# 18650_tester_5.net
KiCad netlist of a schematic drawn in EAGLE
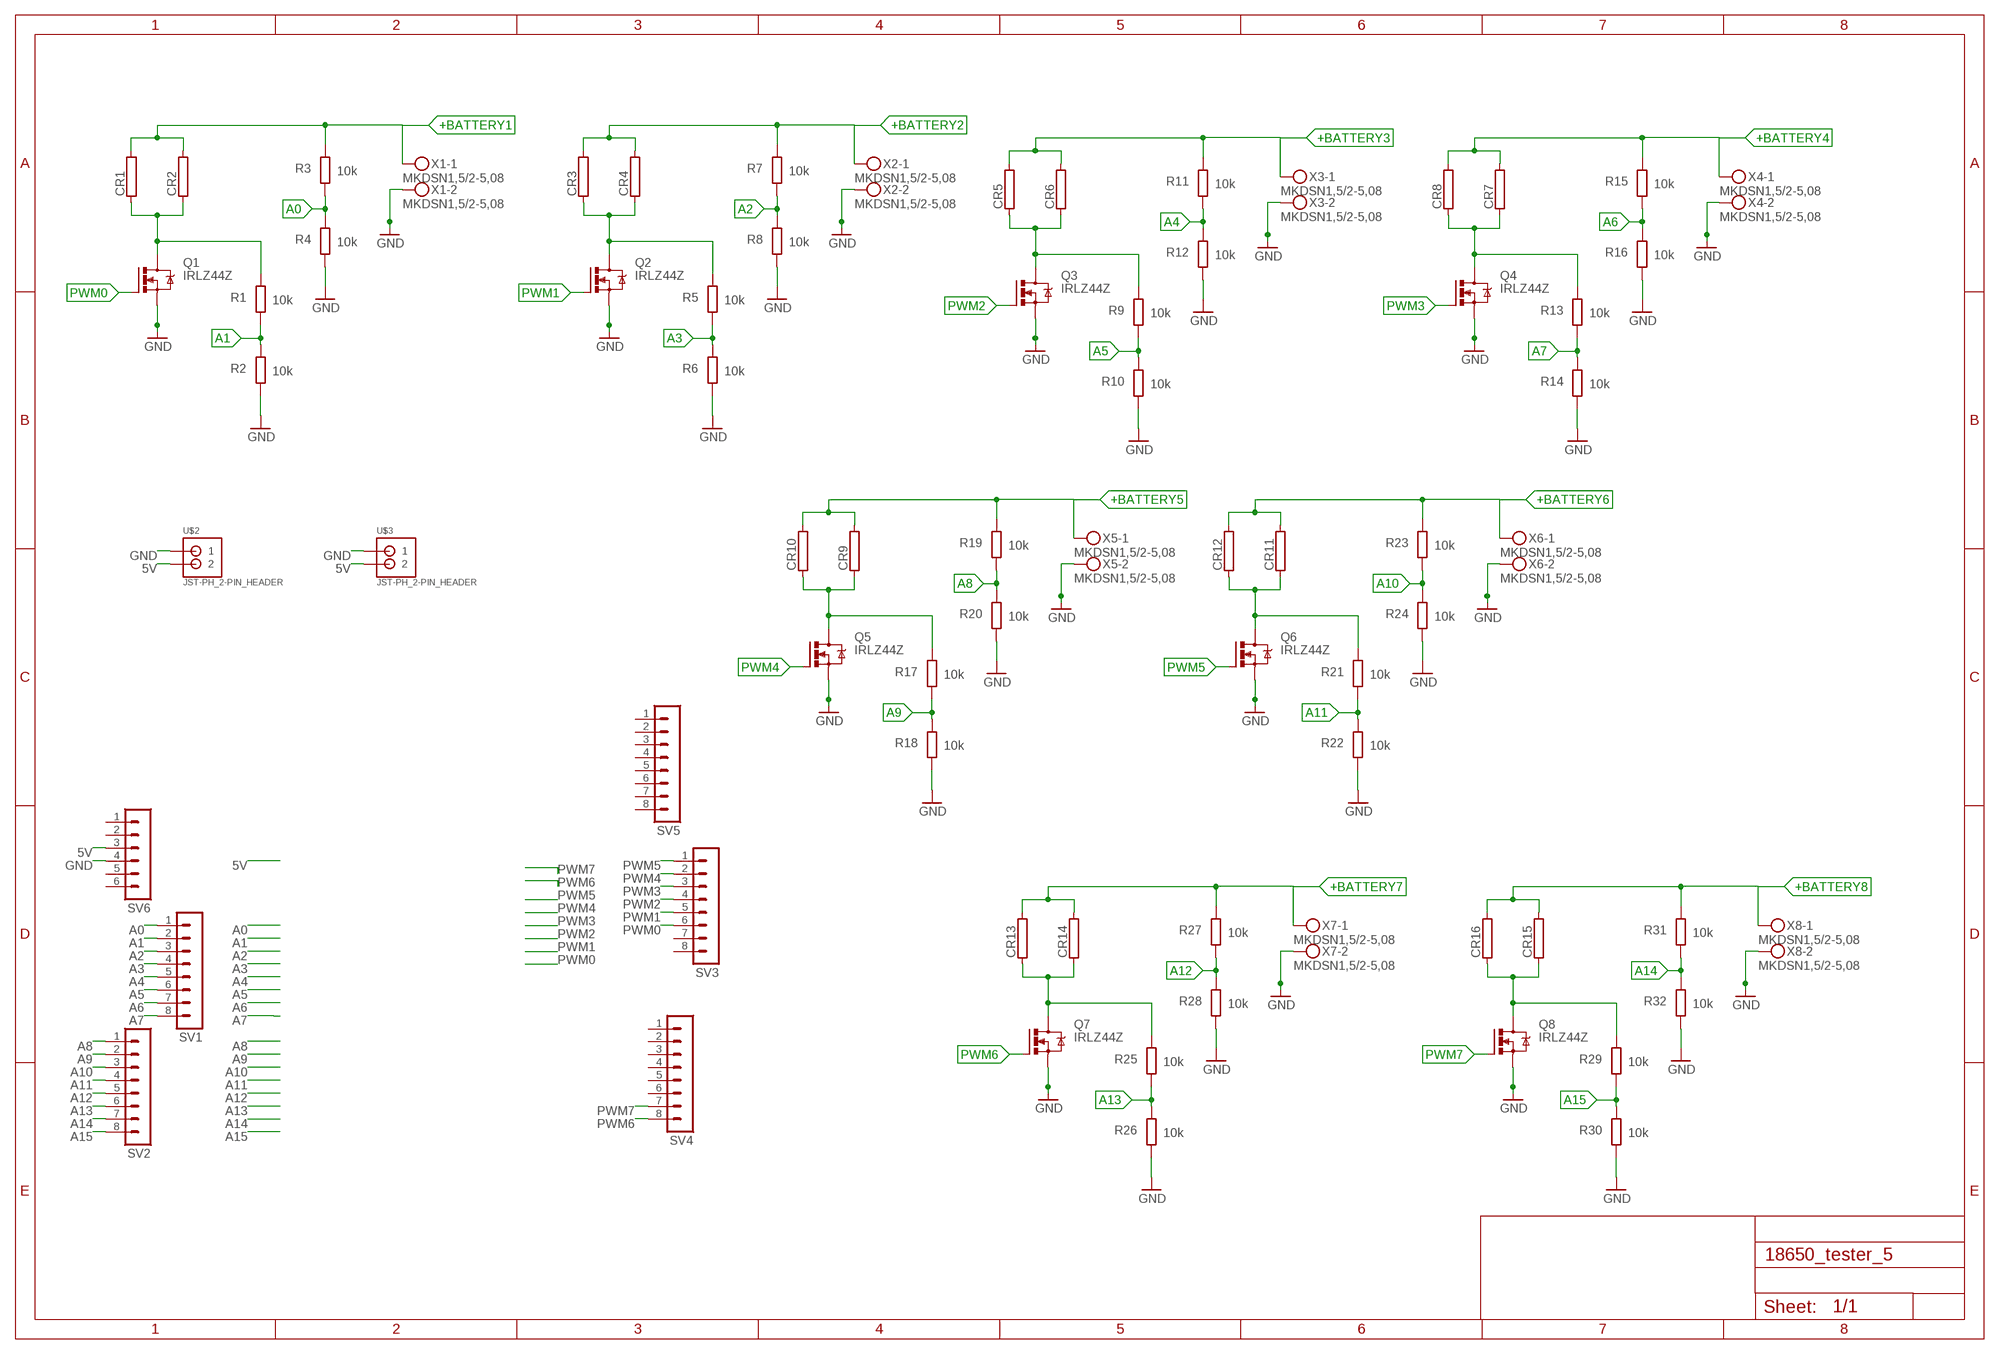
[diagram p0: schematic, sheet 1]

(export (version "E")
  (design (tool "Eeschema 10.0.6"))
  (components
    (comp (ref "CR1")
      (value "RRWM6X22")
      (footprint "eagle-import:RWM6X22")
      (libsource (lib "eagle-import") (part "RRWM6X22"))
    )
    (comp (ref "CR2")
      (value "RRWM6X22")
      (footprint "eagle-import:RWM6X22")
      (libsource (lib "eagle-import") (part "RRWM6X22"))
    )
    (comp (ref "CR3")
      (value "RRWM6X22")
      (footprint "eagle-import:RWM6X22")
      (libsource (lib "eagle-import") (part "RRWM6X22"))
    )
    (comp (ref "CR4")
      (value "RRWM6X22")
      (footprint "eagle-import:RWM6X22")
      (libsource (lib "eagle-import") (part "RRWM6X22"))
    )
    (comp (ref "CR5")
      (value "RRWM6X22")
      (footprint "eagle-import:RWM6X22")
      (libsource (lib "eagle-import") (part "RRWM6X22"))
    )
    (comp (ref "CR6")
      (value "RRWM6X22")
      (footprint "eagle-import:RWM6X22")
      (libsource (lib "eagle-import") (part "RRWM6X22"))
    )
    (comp (ref "CR7")
      (value "RRWM6X22")
      (footprint "eagle-import:RWM6X22")
      (libsource (lib "eagle-import") (part "RRWM6X22"))
    )
    (comp (ref "CR8")
      (value "RRWM6X22")
      (footprint "eagle-import:RWM6X22")
      (libsource (lib "eagle-import") (part "RRWM6X22"))
    )
    (comp (ref "CR9")
      (value "RRWM6X22")
      (footprint "eagle-import:RWM6X22")
      (libsource (lib "eagle-import") (part "RRWM6X22"))
    )
    (comp (ref "CR10")
      (value "RRWM6X22")
      (footprint "eagle-import:RWM6X22")
      (libsource (lib "eagle-import") (part "RRWM6X22"))
    )
    (comp (ref "CR11")
      (value "RRWM6X22")
      (footprint "eagle-import:RWM6X22")
      (libsource (lib "eagle-import") (part "RRWM6X22"))
    )
    (comp (ref "CR12")
      (value "RRWM6X22")
      (footprint "eagle-import:RWM6X22")
      (libsource (lib "eagle-import") (part "RRWM6X22"))
    )
    (comp (ref "CR13")
      (value "RRWM6X22")
      (footprint "eagle-import:RWM6X22")
      (libsource (lib "eagle-import") (part "RRWM6X22"))
    )
    (comp (ref "CR14")
      (value "RRWM6X22")
      (footprint "eagle-import:RWM6X22")
      (libsource (lib "eagle-import") (part "RRWM6X22"))
    )
    (comp (ref "CR15")
      (value "RRWM6X22")
      (footprint "eagle-import:RWM6X22")
      (libsource (lib "eagle-import") (part "RRWM6X22"))
    )
    (comp (ref "CR16")
      (value "RRWM6X22")
      (footprint "eagle-import:RWM6X22")
      (libsource (lib "eagle-import") (part "RRWM6X22"))
    )
    (comp (ref "Q1")
      (value "IRLZ44Z")
      (footprint "eagle-import:TO220BH")
      (libsource (lib "eagle-import") (part "IRLZ44Z"))
    )
    (comp (ref "Q2")
      (value "IRLZ44Z")
      (footprint "eagle-import:TO220BH")
      (libsource (lib "eagle-import") (part "IRLZ44Z"))
    )
    (comp (ref "Q3")
      (value "IRLZ44Z")
      (footprint "eagle-import:TO220BH")
      (libsource (lib "eagle-import") (part "IRLZ44Z"))
    )
    (comp (ref "Q4")
      (value "IRLZ44Z")
      (footprint "eagle-import:TO220BH")
      (libsource (lib "eagle-import") (part "IRLZ44Z"))
    )
    (comp (ref "Q5")
      (value "IRLZ44Z")
      (footprint "eagle-import:TO220BH")
      (libsource (lib "eagle-import") (part "IRLZ44Z"))
    )
    (comp (ref "Q6")
      (value "IRLZ44Z")
      (footprint "eagle-import:TO220BH")
      (libsource (lib "eagle-import") (part "IRLZ44Z"))
    )
    (comp (ref "Q7")
      (value "IRLZ44Z")
      (footprint "eagle-import:TO220BH")
      (libsource (lib "eagle-import") (part "IRLZ44Z"))
    )
    (comp (ref "Q8")
      (value "IRLZ44Z")
      (footprint "eagle-import:TO220BH")
      (libsource (lib "eagle-import") (part "IRLZ44Z"))
    )
    (comp (ref "R1")
      (value "10k")
      (footprint "eagle-import:M1206")
      (libsource (lib "eagle-import") (part "R-EU_M1206"))
    )
    (comp (ref "R2")
      (value "10k")
      (footprint "eagle-import:M1206")
      (libsource (lib "eagle-import") (part "R-EU_M1206"))
    )
    (comp (ref "R3")
      (value "10k")
      (footprint "eagle-import:M1206")
      (libsource (lib "eagle-import") (part "R-EU_M1206"))
    )
    (comp (ref "R4")
      (value "10k")
      (footprint "eagle-import:M1206")
      (libsource (lib "eagle-import") (part "R-EU_M1206"))
    )
    (comp (ref "R5")
      (value "10k")
      (footprint "eagle-import:M1206")
      (libsource (lib "eagle-import") (part "R-EU_M1206"))
    )
    (comp (ref "R6")
      (value "10k")
      (footprint "eagle-import:M1206")
      (libsource (lib "eagle-import") (part "R-EU_M1206"))
    )
    (comp (ref "R7")
      (value "10k")
      (footprint "eagle-import:M1206")
      (libsource (lib "eagle-import") (part "R-EU_M1206"))
    )
    (comp (ref "R8")
      (value "10k")
      (footprint "eagle-import:M1206")
      (libsource (lib "eagle-import") (part "R-EU_M1206"))
    )
    (comp (ref "R9")
      (value "10k")
      (footprint "eagle-import:M1206")
      (libsource (lib "eagle-import") (part "R-EU_M1206"))
    )
    (comp (ref "R10")
      (value "10k")
      (footprint "eagle-import:M1206")
      (libsource (lib "eagle-import") (part "R-EU_M1206"))
    )
    (comp (ref "R11")
      (value "10k")
      (footprint "eagle-import:M1206")
      (libsource (lib "eagle-import") (part "R-EU_M1206"))
    )
    (comp (ref "R12")
      (value "10k")
      (footprint "eagle-import:M1206")
      (libsource (lib "eagle-import") (part "R-EU_M1206"))
    )
    (comp (ref "R13")
      (value "10k")
      (footprint "eagle-import:M1206")
      (libsource (lib "eagle-import") (part "R-EU_M1206"))
    )
    (comp (ref "R14")
      (value "10k")
      (footprint "eagle-import:M1206")
      (libsource (lib "eagle-import") (part "R-EU_M1206"))
    )
    (comp (ref "R15")
      (value "10k")
      (footprint "eagle-import:M1206")
      (libsource (lib "eagle-import") (part "R-EU_M1206"))
    )
    (comp (ref "R16")
      (value "10k")
      (footprint "eagle-import:M1206")
      (libsource (lib "eagle-import") (part "R-EU_M1206"))
    )
    (comp (ref "R17")
      (value "10k")
      (footprint "eagle-import:M1206")
      (libsource (lib "eagle-import") (part "R-EU_M1206"))
    )
    (comp (ref "R18")
      (value "10k")
      (footprint "eagle-import:M1206")
      (libsource (lib "eagle-import") (part "R-EU_M1206"))
    )
    (comp (ref "R19")
      (value "10k")
      (footprint "eagle-import:M1206")
      (libsource (lib "eagle-import") (part "R-EU_M1206"))
    )
    (comp (ref "R20")
      (value "10k")
      (footprint "eagle-import:M1206")
      (libsource (lib "eagle-import") (part "R-EU_M1206"))
    )
    (comp (ref "R21")
      (value "10k")
      (footprint "eagle-import:M1206")
      (libsource (lib "eagle-import") (part "R-EU_M1206"))
    )
    (comp (ref "R22")
      (value "10k")
      (footprint "eagle-import:M1206")
      (libsource (lib "eagle-import") (part "R-EU_M1206"))
    )
    (comp (ref "R23")
      (value "10k")
      (footprint "eagle-import:M1206")
      (libsource (lib "eagle-import") (part "R-EU_M1206"))
    )
    (comp (ref "R24")
      (value "10k")
      (footprint "eagle-import:M1206")
      (libsource (lib "eagle-import") (part "R-EU_M1206"))
    )
    (comp (ref "R25")
      (value "10k")
      (footprint "eagle-import:M1206")
      (libsource (lib "eagle-import") (part "R-EU_M1206"))
    )
    (comp (ref "R26")
      (value "10k")
      (footprint "eagle-import:M1206")
      (libsource (lib "eagle-import") (part "R-EU_M1206"))
    )
    (comp (ref "R27")
      (value "10k")
      (footprint "eagle-import:M1206")
      (libsource (lib "eagle-import") (part "R-EU_M1206"))
    )
    (comp (ref "R28")
      (value "10k")
      (footprint "eagle-import:M1206")
      (libsource (lib "eagle-import") (part "R-EU_M1206"))
    )
    (comp (ref "R29")
      (value "10k")
      (footprint "eagle-import:M1206")
      (libsource (lib "eagle-import") (part "R-EU_M1206"))
    )
    (comp (ref "R30")
      (value "10k")
      (footprint "eagle-import:M1206")
      (libsource (lib "eagle-import") (part "R-EU_M1206"))
    )
    (comp (ref "R31")
      (value "10k")
      (footprint "eagle-import:M1206")
      (libsource (lib "eagle-import") (part "R-EU_M1206"))
    )
    (comp (ref "R32")
      (value "10k")
      (footprint "eagle-import:M1206")
      (libsource (lib "eagle-import") (part "R-EU_M1206"))
    )
    (comp (ref "SV1")
      (value "MA08-1")
      (footprint "eagle-import:MA08-1")
      (libsource (lib "eagle-import") (part "MA08-1"))
    )
    (comp (ref "SV2")
      (value "MA08-1")
      (footprint "eagle-import:MA08-1")
      (libsource (lib "eagle-import") (part "MA08-1"))
    )
    (comp (ref "SV3")
      (value "MA08-1")
      (footprint "eagle-import:MA08-1")
      (libsource (lib "eagle-import") (part "MA08-1"))
    )
    (comp (ref "SV4")
      (value "MA08-1")
      (footprint "eagle-import:MA08-1")
      (libsource (lib "eagle-import") (part "MA08-1"))
    )
    (comp (ref "SV5")
      (value "MA08-1")
      (footprint "eagle-import:MA08-1")
      (libsource (lib "eagle-import") (part "MA08-1"))
    )
    (comp (ref "SV6")
      (value "MA06-1")
      (footprint "eagle-import:MA06-1")
      (libsource (lib "eagle-import") (part "MA06-1"))
    )
    (comp (ref "U$2")
      (value "JST-PH_2-PIN_HEADER")
      (footprint "eagle-import:JST_B2B-PH_HEADER")
      (libsource (lib "eagle-import") (part "JST-PH_2-PIN_HEADER"))
    )
    (comp (ref "U$3")
      (value "JST-PH_2-PIN_HEADER")
      (footprint "eagle-import:JST_B2B-PH_HEADER")
      (libsource (lib "eagle-import") (part "JST-PH_2-PIN_HEADER"))
    )
    (comp (ref "X1")
      (value "MKDSN1,5/2-5,08")
      (footprint "eagle-import:MKDSN1,5_2-5,08")
      (libsource (lib "eagle-import") (part "MKDSN1,5/2-5,08"))
    )
    (comp (ref "X2")
      (value "MKDSN1,5/2-5,08")
      (footprint "eagle-import:MKDSN1,5_2-5,08")
      (libsource (lib "eagle-import") (part "MKDSN1,5/2-5,08"))
    )
    (comp (ref "X3")
      (value "MKDSN1,5/2-5,08")
      (footprint "eagle-import:MKDSN1,5_2-5,08")
      (libsource (lib "eagle-import") (part "MKDSN1,5/2-5,08"))
    )
    (comp (ref "X4")
      (value "MKDSN1,5/2-5,08")
      (footprint "eagle-import:MKDSN1,5_2-5,08")
      (libsource (lib "eagle-import") (part "MKDSN1,5/2-5,08"))
    )
    (comp (ref "X5")
      (value "MKDSN1,5/2-5,08")
      (footprint "eagle-import:MKDSN1,5_2-5,08")
      (libsource (lib "eagle-import") (part "MKDSN1,5/2-5,08"))
    )
    (comp (ref "X6")
      (value "MKDSN1,5/2-5,08")
      (footprint "eagle-import:MKDSN1,5_2-5,08")
      (libsource (lib "eagle-import") (part "MKDSN1,5/2-5,08"))
    )
    (comp (ref "X7")
      (value "MKDSN1,5/2-5,08")
      (footprint "eagle-import:MKDSN1,5_2-5,08")
      (libsource (lib "eagle-import") (part "MKDSN1,5/2-5,08"))
    )
    (comp (ref "X8")
      (value "MKDSN1,5/2-5,08")
      (footprint "eagle-import:MKDSN1,5_2-5,08")
      (libsource (lib "eagle-import") (part "MKDSN1,5/2-5,08"))
    )
  )
  (nets
    (net (code "1") (name "+BATTERY1") (class "Default")
      (node (ref "CR1") (pin "2") (pinfunction "2_2") (pintype "passive"))
      (node (ref "CR2") (pin "2") (pinfunction "2_2") (pintype "passive"))
      (node (ref "R3") (pin "2") (pinfunction "2_2") (pintype "passive"))
      (node (ref "X1") (pin "1") (pinfunction "KL_1") (pintype "passive"))
    )
    (net (code "2") (name "+BATTERY2") (class "Default")
      (node (ref "CR3") (pin "2") (pinfunction "2_2") (pintype "passive"))
      (node (ref "CR4") (pin "2") (pinfunction "2_2") (pintype "passive"))
      (node (ref "R7") (pin "2") (pinfunction "2_2") (pintype "passive"))
      (node (ref "X2") (pin "1") (pinfunction "KL_1") (pintype "passive"))
    )
    (net (code "3") (name "+BATTERY3") (class "Default")
      (node (ref "CR5") (pin "2") (pinfunction "2_2") (pintype "passive"))
      (node (ref "CR6") (pin "2") (pinfunction "2_2") (pintype "passive"))
      (node (ref "R11") (pin "2") (pinfunction "2_2") (pintype "passive"))
      (node (ref "X3") (pin "1") (pinfunction "KL_1") (pintype "passive"))
    )
    (net (code "4") (name "+BATTERY4") (class "Default")
      (node (ref "CR7") (pin "2") (pinfunction "2_2") (pintype "passive"))
      (node (ref "CR8") (pin "2") (pinfunction "2_2") (pintype "passive"))
      (node (ref "R15") (pin "2") (pinfunction "2_2") (pintype "passive"))
      (node (ref "X4") (pin "1") (pinfunction "KL_1") (pintype "passive"))
    )
    (net (code "5") (name "+BATTERY5") (class "Default")
      (node (ref "CR10") (pin "2") (pinfunction "2_2") (pintype "passive"))
      (node (ref "CR9") (pin "2") (pinfunction "2_2") (pintype "passive"))
      (node (ref "R19") (pin "2") (pinfunction "2_2") (pintype "passive"))
      (node (ref "X5") (pin "1") (pinfunction "KL_1") (pintype "passive"))
    )
    (net (code "6") (name "+BATTERY6") (class "Default")
      (node (ref "CR11") (pin "2") (pinfunction "2_2") (pintype "passive"))
      (node (ref "CR12") (pin "2") (pinfunction "2_2") (pintype "passive"))
      (node (ref "R23") (pin "2") (pinfunction "2_2") (pintype "passive"))
      (node (ref "X6") (pin "1") (pinfunction "KL_1") (pintype "passive"))
    )
    (net (code "7") (name "+BATTERY7") (class "Default")
      (node (ref "CR13") (pin "2") (pinfunction "2_2") (pintype "passive"))
      (node (ref "CR14") (pin "2") (pinfunction "2_2") (pintype "passive"))
      (node (ref "R27") (pin "2") (pinfunction "2_2") (pintype "passive"))
      (node (ref "X7") (pin "1") (pinfunction "KL_1") (pintype "passive"))
    )
    (net (code "8") (name "+BATTERY8") (class "Default")
      (node (ref "CR15") (pin "2") (pinfunction "2_2") (pintype "passive"))
      (node (ref "CR16") (pin "2") (pinfunction "2_2") (pintype "passive"))
      (node (ref "R31") (pin "2") (pinfunction "2_2") (pintype "passive"))
      (node (ref "X8") (pin "1") (pinfunction "KL_1") (pintype "passive"))
    )
    (net (code "9") (name "/5V") (class "Default")
      (node (ref "SV6") (pin "3") (pinfunction "3_3") (pintype "passive"))
      (node (ref "U$2") (pin "P2") (pinfunction "2_P2") (pintype "bidirectional"))
      (node (ref "U$3") (pin "P2") (pinfunction "2_P2") (pintype "bidirectional"))
    )
    (net (code "10") (name "A0") (class "Default")
      (node (ref "R3") (pin "1") (pinfunction "1_1") (pintype "passive"))
      (node (ref "R4") (pin "2") (pinfunction "2_2") (pintype "passive"))
      (node (ref "SV1") (pin "1") (pinfunction "1_1") (pintype "passive"))
    )
    (net (code "11") (name "A1") (class "Default")
      (node (ref "R1") (pin "1") (pinfunction "1_1") (pintype "passive"))
      (node (ref "R2") (pin "2") (pinfunction "2_2") (pintype "passive"))
      (node (ref "SV1") (pin "2") (pinfunction "2_2") (pintype "passive"))
    )
    (net (code "12") (name "A2") (class "Default")
      (node (ref "R7") (pin "1") (pinfunction "1_1") (pintype "passive"))
      (node (ref "R8") (pin "2") (pinfunction "2_2") (pintype "passive"))
      (node (ref "SV1") (pin "3") (pinfunction "3_3") (pintype "passive"))
    )
    (net (code "13") (name "A3") (class "Default")
      (node (ref "R5") (pin "1") (pinfunction "1_1") (pintype "passive"))
      (node (ref "R6") (pin "2") (pinfunction "2_2") (pintype "passive"))
      (node (ref "SV1") (pin "4") (pinfunction "4_4") (pintype "passive"))
    )
    (net (code "14") (name "A4") (class "Default")
      (node (ref "R11") (pin "1") (pinfunction "1_1") (pintype "passive"))
      (node (ref "R12") (pin "2") (pinfunction "2_2") (pintype "passive"))
      (node (ref "SV1") (pin "5") (pinfunction "5_5") (pintype "passive"))
    )
    (net (code "15") (name "A5") (class "Default")
      (node (ref "R10") (pin "2") (pinfunction "2_2") (pintype "passive"))
      (node (ref "R9") (pin "1") (pinfunction "1_1") (pintype "passive"))
      (node (ref "SV1") (pin "6") (pinfunction "6_6") (pintype "passive"))
    )
    (net (code "16") (name "A6") (class "Default")
      (node (ref "R15") (pin "1") (pinfunction "1_1") (pintype "passive"))
      (node (ref "R16") (pin "2") (pinfunction "2_2") (pintype "passive"))
      (node (ref "SV1") (pin "7") (pinfunction "7_7") (pintype "passive"))
    )
    (net (code "17") (name "A7") (class "Default")
      (node (ref "R13") (pin "1") (pinfunction "1_1") (pintype "passive"))
      (node (ref "R14") (pin "2") (pinfunction "2_2") (pintype "passive"))
      (node (ref "SV1") (pin "8") (pinfunction "8_8") (pintype "passive"))
    )
    (net (code "18") (name "A8") (class "Default")
      (node (ref "R19") (pin "1") (pinfunction "1_1") (pintype "passive"))
      (node (ref "R20") (pin "2") (pinfunction "2_2") (pintype "passive"))
      (node (ref "SV2") (pin "1") (pinfunction "1_1") (pintype "passive"))
    )
    (net (code "19") (name "A9") (class "Default")
      (node (ref "R17") (pin "1") (pinfunction "1_1") (pintype "passive"))
      (node (ref "R18") (pin "2") (pinfunction "2_2") (pintype "passive"))
      (node (ref "SV2") (pin "2") (pinfunction "2_2") (pintype "passive"))
    )
    (net (code "20") (name "A10") (class "Default")
      (node (ref "R23") (pin "1") (pinfunction "1_1") (pintype "passive"))
      (node (ref "R24") (pin "2") (pinfunction "2_2") (pintype "passive"))
      (node (ref "SV2") (pin "3") (pinfunction "3_3") (pintype "passive"))
    )
    (net (code "21") (name "A11") (class "Default")
      (node (ref "R21") (pin "1") (pinfunction "1_1") (pintype "passive"))
      (node (ref "R22") (pin "2") (pinfunction "2_2") (pintype "passive"))
      (node (ref "SV2") (pin "4") (pinfunction "4_4") (pintype "passive"))
    )
    (net (code "22") (name "A12") (class "Default")
      (node (ref "R27") (pin "1") (pinfunction "1_1") (pintype "passive"))
      (node (ref "R28") (pin "2") (pinfunction "2_2") (pintype "passive"))
      (node (ref "SV2") (pin "5") (pinfunction "5_5") (pintype "passive"))
    )
    (net (code "23") (name "A13") (class "Default")
      (node (ref "R25") (pin "1") (pinfunction "1_1") (pintype "passive"))
      (node (ref "R26") (pin "2") (pinfunction "2_2") (pintype "passive"))
      (node (ref "SV2") (pin "6") (pinfunction "6_6") (pintype "passive"))
    )
    (net (code "24") (name "A14") (class "Default")
      (node (ref "R31") (pin "1") (pinfunction "1_1") (pintype "passive"))
      (node (ref "R32") (pin "2") (pinfunction "2_2") (pintype "passive"))
      (node (ref "SV2") (pin "7") (pinfunction "7_7") (pintype "passive"))
    )
    (net (code "25") (name "A15") (class "Default")
      (node (ref "R29") (pin "1") (pinfunction "1_1") (pintype "passive"))
      (node (ref "R30") (pin "2") (pinfunction "2_2") (pintype "passive"))
      (node (ref "SV2") (pin "8") (pinfunction "8_8") (pintype "passive"))
    )
    (net (code "26") (name "GND") (class "Default")
      (node (ref "Q1") (pin "S") (pinfunction "S_S") (pintype "passive"))
      (node (ref "Q2") (pin "S") (pinfunction "S_S") (pintype "passive"))
      (node (ref "Q3") (pin "S") (pinfunction "S_S") (pintype "passive"))
      (node (ref "Q4") (pin "S") (pinfunction "S_S") (pintype "passive"))
      (node (ref "Q5") (pin "S") (pinfunction "S_S") (pintype "passive"))
      (node (ref "Q6") (pin "S") (pinfunction "S_S") (pintype "passive"))
      (node (ref "Q7") (pin "S") (pinfunction "S_S") (pintype "passive"))
      (node (ref "Q8") (pin "S") (pinfunction "S_S") (pintype "passive"))
      (node (ref "R10") (pin "1") (pinfunction "1_1") (pintype "passive"))
      (node (ref "R12") (pin "1") (pinfunction "1_1") (pintype "passive"))
      (node (ref "R14") (pin "1") (pinfunction "1_1") (pintype "passive"))
      (node (ref "R16") (pin "1") (pinfunction "1_1") (pintype "passive"))
      (node (ref "R18") (pin "1") (pinfunction "1_1") (pintype "passive"))
      (node (ref "R2") (pin "1") (pinfunction "1_1") (pintype "passive"))
      (node (ref "R20") (pin "1") (pinfunction "1_1") (pintype "passive"))
      (node (ref "R22") (pin "1") (pinfunction "1_1") (pintype "passive"))
      (node (ref "R24") (pin "1") (pinfunction "1_1") (pintype "passive"))
      (node (ref "R26") (pin "1") (pinfunction "1_1") (pintype "passive"))
      (node (ref "R28") (pin "1") (pinfunction "1_1") (pintype "passive"))
      (node (ref "R30") (pin "1") (pinfunction "1_1") (pintype "passive"))
      (node (ref "R32") (pin "1") (pinfunction "1_1") (pintype "passive"))
      (node (ref "R4") (pin "1") (pinfunction "1_1") (pintype "passive"))
      (node (ref "R6") (pin "1") (pinfunction "1_1") (pintype "passive"))
      (node (ref "R8") (pin "1") (pinfunction "1_1") (pintype "passive"))
      (node (ref "SV6") (pin "4") (pinfunction "4_4") (pintype "passive"))
      (node (ref "U$2") (pin "P1") (pinfunction "1_P1") (pintype "bidirectional"))
      (node (ref "U$3") (pin "P1") (pinfunction "1_P1") (pintype "bidirectional"))
      (node (ref "X1") (pin "2") (pinfunction "KL_2") (pintype "passive"))
      (node (ref "X2") (pin "2") (pinfunction "KL_2") (pintype "passive"))
      (node (ref "X3") (pin "2") (pinfunction "KL_2") (pintype "passive"))
      (node (ref "X4") (pin "2") (pinfunction "KL_2") (pintype "passive"))
      (node (ref "X5") (pin "2") (pinfunction "KL_2") (pintype "passive"))
      (node (ref "X6") (pin "2") (pinfunction "KL_2") (pintype "passive"))
      (node (ref "X7") (pin "2") (pinfunction "KL_2") (pintype "passive"))
      (node (ref "X8") (pin "2") (pinfunction "KL_2") (pintype "passive"))
    )
    (net (code "27") (name "Net-(CR1-Pad1)") (class "Default")
      (node (ref "CR1") (pin "1") (pinfunction "1_1") (pintype "passive"))
      (node (ref "CR2") (pin "1") (pinfunction "1_1") (pintype "passive"))
      (node (ref "Q1") (pin "D") (pinfunction "D_D") (pintype "passive"))
      (node (ref "R1") (pin "2") (pinfunction "2_2") (pintype "passive"))
    )
    (net (code "28") (name "Net-(CR3-Pad1)") (class "Default")
      (node (ref "CR3") (pin "1") (pinfunction "1_1") (pintype "passive"))
      (node (ref "CR4") (pin "1") (pinfunction "1_1") (pintype "passive"))
      (node (ref "Q2") (pin "D") (pinfunction "D_D") (pintype "passive"))
      (node (ref "R5") (pin "2") (pinfunction "2_2") (pintype "passive"))
    )
    (net (code "29") (name "Net-(CR5-Pad1)") (class "Default")
      (node (ref "CR5") (pin "1") (pinfunction "1_1") (pintype "passive"))
      (node (ref "CR6") (pin "1") (pinfunction "1_1") (pintype "passive"))
      (node (ref "Q3") (pin "D") (pinfunction "D_D") (pintype "passive"))
      (node (ref "R9") (pin "2") (pinfunction "2_2") (pintype "passive"))
    )
    (net (code "30") (name "Net-(CR7-Pad1)") (class "Default")
      (node (ref "CR7") (pin "1") (pinfunction "1_1") (pintype "passive"))
      (node (ref "CR8") (pin "1") (pinfunction "1_1") (pintype "passive"))
      (node (ref "Q4") (pin "D") (pinfunction "D_D") (pintype "passive"))
      (node (ref "R13") (pin "2") (pinfunction "2_2") (pintype "passive"))
    )
    (net (code "31") (name "Net-(CR10-Pad1)") (class "Default")
      (node (ref "CR10") (pin "1") (pinfunction "1_1") (pintype "passive"))
      (node (ref "CR9") (pin "1") (pinfunction "1_1") (pintype "passive"))
      (node (ref "Q5") (pin "D") (pinfunction "D_D") (pintype "passive"))
      (node (ref "R17") (pin "2") (pinfunction "2_2") (pintype "passive"))
    )
    (net (code "32") (name "Net-(CR11-Pad1)") (class "Default")
      (node (ref "CR11") (pin "1") (pinfunction "1_1") (pintype "passive"))
      (node (ref "CR12") (pin "1") (pinfunction "1_1") (pintype "passive"))
      (node (ref "Q6") (pin "D") (pinfunction "D_D") (pintype "passive"))
      (node (ref "R21") (pin "2") (pinfunction "2_2") (pintype "passive"))
    )
    (net (code "33") (name "Net-(CR13-Pad1)") (class "Default")
      (node (ref "CR13") (pin "1") (pinfunction "1_1") (pintype "passive"))
      (node (ref "CR14") (pin "1") (pinfunction "1_1") (pintype "passive"))
      (node (ref "Q7") (pin "D") (pinfunction "D_D") (pintype "passive"))
      (node (ref "R25") (pin "2") (pinfunction "2_2") (pintype "passive"))
    )
    (net (code "34") (name "Net-(CR15-Pad1)") (class "Default")
      (node (ref "CR15") (pin "1") (pinfunction "1_1") (pintype "passive"))
      (node (ref "CR16") (pin "1") (pinfunction "1_1") (pintype "passive"))
      (node (ref "Q8") (pin "D") (pinfunction "D_D") (pintype "passive"))
      (node (ref "R29") (pin "2") (pinfunction "2_2") (pintype "passive"))
    )
    (net (code "35") (name "PWM0") (class "Default")
      (node (ref "Q1") (pin "G") (pinfunction "G_G") (pintype "passive"))
      (node (ref "SV3") (pin "6") (pinfunction "6_6") (pintype "passive"))
    )
    (net (code "36") (name "PWM1") (class "Default")
      (node (ref "Q2") (pin "G") (pinfunction "G_G") (pintype "passive"))
      (node (ref "SV3") (pin "5") (pinfunction "5_5") (pintype "passive"))
    )
    (net (code "37") (name "PWM2") (class "Default")
      (node (ref "Q3") (pin "G") (pinfunction "G_G") (pintype "passive"))
      (node (ref "SV3") (pin "4") (pinfunction "4_4") (pintype "passive"))
    )
    (net (code "38") (name "PWM3") (class "Default")
      (node (ref "Q4") (pin "G") (pinfunction "G_G") (pintype "passive"))
      (node (ref "SV3") (pin "3") (pinfunction "3_3") (pintype "passive"))
    )
    (net (code "39") (name "PWM4") (class "Default")
      (node (ref "Q5") (pin "G") (pinfunction "G_G") (pintype "passive"))
      (node (ref "SV3") (pin "2") (pinfunction "2_2") (pintype "passive"))
    )
    (net (code "40") (name "PWM5") (class "Default")
      (node (ref "Q6") (pin "G") (pinfunction "G_G") (pintype "passive"))
      (node (ref "SV3") (pin "1") (pinfunction "1_1") (pintype "passive"))
    )
    (net (code "41") (name "PWM6") (class "Default")
      (node (ref "Q7") (pin "G") (pinfunction "G_G") (pintype "passive"))
      (node (ref "SV4") (pin "8") (pinfunction "8_8") (pintype "passive"))
    )
    (net (code "42") (name "PWM7") (class "Default")
      (node (ref "Q8") (pin "G") (pinfunction "G_G") (pintype "passive"))
      (node (ref "SV4") (pin "7") (pinfunction "7_7") (pintype "passive"))
    )
    (net (code "43") (name "unconnected-(SV3-Pad7)") (class "Default")
      (node (ref "SV3") (pin "7") (pinfunction "7_7") (pintype "passive"))
    )
    (net (code "44") (name "unconnected-(SV3-Pad8)") (class "Default")
      (node (ref "SV3") (pin "8") (pinfunction "8_8") (pintype "passive"))
    )
    (net (code "45") (name "unconnected-(SV4-Pad1)") (class "Default")
      (node (ref "SV4") (pin "1") (pinfunction "1_1") (pintype "passive"))
    )
    (net (code "46") (name "unconnected-(SV4-Pad2)") (class "Default")
      (node (ref "SV4") (pin "2") (pinfunction "2_2") (pintype "passive"))
    )
    (net (code "47") (name "unconnected-(SV4-Pad3)") (class "Default")
      (node (ref "SV4") (pin "3") (pinfunction "3_3") (pintype "passive"))
    )
    (net (code "48") (name "unconnected-(SV4-Pad4)") (class "Default")
      (node (ref "SV4") (pin "4") (pinfunction "4_4") (pintype "passive"))
    )
    (net (code "49") (name "unconnected-(SV4-Pad5)") (class "Default")
      (node (ref "SV4") (pin "5") (pinfunction "5_5") (pintype "passive"))
    )
    (net (code "50") (name "unconnected-(SV4-Pad6)") (class "Default")
      (node (ref "SV4") (pin "6") (pinfunction "6_6") (pintype "passive"))
    )
    (net (code "51") (name "unconnected-(SV5-Pad1)") (class "Default")
      (node (ref "SV5") (pin "1") (pinfunction "1_1") (pintype "passive"))
    )
    (net (code "52") (name "unconnected-(SV5-Pad2)") (class "Default")
      (node (ref "SV5") (pin "2") (pinfunction "2_2") (pintype "passive"))
    )
    (net (code "53") (name "unconnected-(SV5-Pad3)") (class "Default")
      (node (ref "SV5") (pin "3") (pinfunction "3_3") (pintype "passive"))
    )
    (net (code "54") (name "unconnected-(SV5-Pad4)") (class "Default")
      (node (ref "SV5") (pin "4") (pinfunction "4_4") (pintype "passive"))
    )
    (net (code "55") (name "unconnected-(SV5-Pad5)") (class "Default")
      (node (ref "SV5") (pin "5") (pinfunction "5_5") (pintype "passive"))
    )
    (net (code "56") (name "unconnected-(SV5-Pad6)") (class "Default")
      (node (ref "SV5") (pin "6") (pinfunction "6_6") (pintype "passive"))
    )
    (net (code "57") (name "unconnected-(SV5-Pad7)") (class "Default")
      (node (ref "SV5") (pin "7") (pinfunction "7_7") (pintype "passive"))
    )
    (net (code "58") (name "unconnected-(SV5-Pad8)") (class "Default")
      (node (ref "SV5") (pin "8") (pinfunction "8_8") (pintype "passive"))
    )
    (net (code "59") (name "unconnected-(SV6-Pad1)") (class "Default")
      (node (ref "SV6") (pin "1") (pinfunction "1_1") (pintype "passive"))
    )
    (net (code "60") (name "unconnected-(SV6-Pad2)") (class "Default")
      (node (ref "SV6") (pin "2") (pinfunction "2_2") (pintype "passive"))
    )
    (net (code "61") (name "unconnected-(SV6-Pad5)") (class "Default")
      (node (ref "SV6") (pin "5") (pinfunction "5_5") (pintype "passive"))
    )
    (net (code "62") (name "unconnected-(SV6-Pad6)") (class "Default")
      (node (ref "SV6") (pin "6") (pinfunction "6_6") (pintype "passive"))
    )
  )
)
